# board.net
KiCad netlist of a schematic drawn in EAGLE
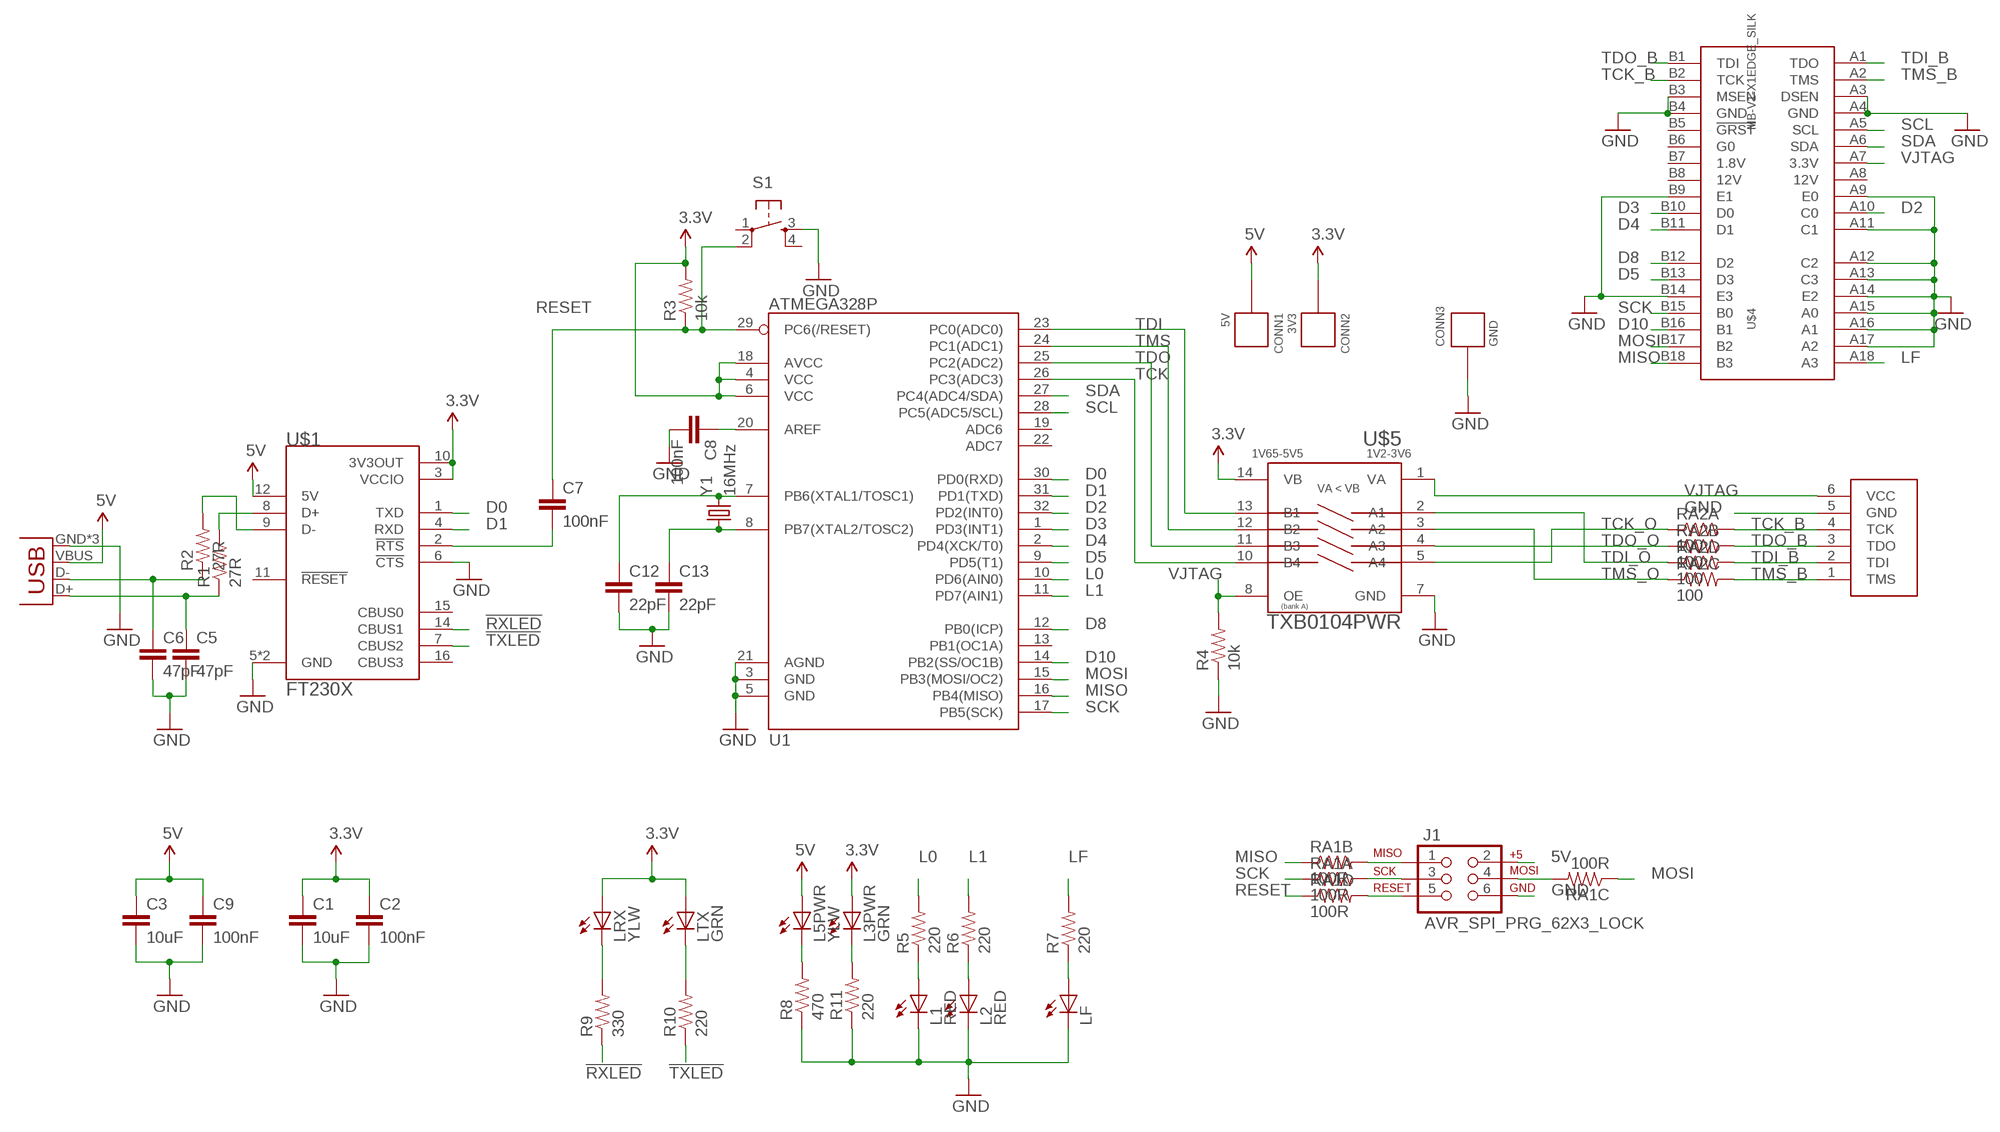
[diagram p0: schematic, sheet 1]

(export (version "E")
  (design (tool "Eeschema 10.0.6"))
  (components
    (comp (ref "C1")
      (value "10uF")
      (footprint "eagle-import:0805")
      (libsource (lib "eagle-import") (part "CAP0805"))
    )
    (comp (ref "C2")
      (value "100nF")
      (footprint "eagle-import:0402-CAP")
      (libsource (lib "eagle-import") (part "CAP0402-CAP"))
    )
    (comp (ref "C3")
      (value "10uF")
      (footprint "eagle-import:0805")
      (libsource (lib "eagle-import") (part "CAP0805"))
    )
    (comp (ref "C5")
      (value "47pF")
      (footprint "eagle-import:0402-CAP")
      (libsource (lib "eagle-import") (part "CAP0402-CAP"))
    )
    (comp (ref "C6")
      (value "47pF")
      (footprint "eagle-import:0402-CAP")
      (libsource (lib "eagle-import") (part "CAP0402-CAP"))
    )
    (comp (ref "C7")
      (value "100nF")
      (footprint "eagle-import:0402-CAP")
      (libsource (lib "eagle-import") (part "CAP0402-CAP"))
    )
    (comp (ref "C8")
      (value "100nF")
      (footprint "eagle-import:0402-CAP")
      (libsource (lib "eagle-import") (part "CAP0402-CAP"))
    )
    (comp (ref "C9")
      (value "100nF")
      (footprint "eagle-import:0402-CAP")
      (libsource (lib "eagle-import") (part "CAP0402-CAP"))
    )
    (comp (ref "C12")
      (value "22pF")
      (footprint "eagle-import:0402-CAP")
      (libsource (lib "eagle-import") (part "CAP0402-CAP"))
    )
    (comp (ref "C13")
      (value "22pF")
      (footprint "eagle-import:0402-CAP")
      (libsource (lib "eagle-import") (part "CAP0402-CAP"))
    )
    (comp (ref "CONN1")
      (value "5V")
      (footprint "eagle-import:HOLE_22AWG")
      (libsource (lib "eagle-import") (part "CONNECTOR22AWG"))
    )
    (comp (ref "CONN2")
      (value "3V3")
      (footprint "eagle-import:HOLE_22AWG")
      (libsource (lib "eagle-import") (part "CONNECTOR22AWG"))
    )
    (comp (ref "CONN3")
      (value "GND")
      (footprint "eagle-import:HOLE_22AWG")
      (libsource (lib "eagle-import") (part "CONNECTOR22AWG"))
    )
    (comp (ref "J1")
      (value "AVR_SPI_PRG_62X3_LOCK")
      (footprint "eagle-import:2X3_LOCK")
      (libsource (lib "eagle-import") (part "AVR_SPI_PRG_62X3_LOCK"))
    )
    (comp (ref "JP1")
      (value "USB-MICROB")
      (footprint "eagle-import:USB-MICROB")
      (libsource (lib "eagle-import") (part "USB-MICROB"))
    )
    (comp (ref "L1")
      (value "RED")
      (footprint "eagle-import:0603_LED")
      (libsource (lib "eagle-import") (part "LED0603"))
    )
    (comp (ref "L2")
      (value "RED")
      (footprint "eagle-import:0603_LED")
      (libsource (lib "eagle-import") (part "LED0603"))
    )
    (comp (ref "L3PWR")
      (value "GRN")
      (footprint "eagle-import:0603_LED")
      (libsource (lib "eagle-import") (part "LED0603"))
    )
    (comp (ref "L5PWR")
      (value "YLW")
      (footprint "eagle-import:0603_LED")
      (libsource (lib "eagle-import") (part "LED0603"))
    )
    (comp (ref "LF")
      (value "LED0603")
      (footprint "eagle-import:0603_LED")
      (libsource (lib "eagle-import") (part "LED0603"))
    )
    (comp (ref "LRX")
      (value "YLW")
      (footprint "eagle-import:0603_LED")
      (libsource (lib "eagle-import") (part "LED0603"))
    )
    (comp (ref "LTX")
      (value "GRN")
      (footprint "eagle-import:0603_LED")
      (libsource (lib "eagle-import") (part "LED0603"))
    )
    (comp (ref "R1")
      (value "27R")
      (footprint "eagle-import:0603-RES")
      (libsource (lib "eagle-import") (part "RESISTOR0603"))
    )
    (comp (ref "R2")
      (value "27R")
      (footprint "eagle-import:0603-RES")
      (libsource (lib "eagle-import") (part "RESISTOR0603"))
    )
    (comp (ref "R3")
      (value "10k")
      (footprint "eagle-import:0603-RES")
      (libsource (lib "eagle-import") (part "RESISTOR0603"))
    )
    (comp (ref "R4")
      (value "10k")
      (footprint "eagle-import:0603-RES")
      (libsource (lib "eagle-import") (part "RESISTOR0603"))
    )
    (comp (ref "R5")
      (value "220")
      (footprint "eagle-import:0603-RES")
      (libsource (lib "eagle-import") (part "RESISTOR0603"))
    )
    (comp (ref "R6")
      (value "220")
      (footprint "eagle-import:0603-RES")
      (libsource (lib "eagle-import") (part "RESISTOR0603"))
    )
    (comp (ref "R7")
      (value "220")
      (footprint "eagle-import:0603-RES")
      (libsource (lib "eagle-import") (part "RESISTOR0603"))
    )
    (comp (ref "R8")
      (value "470")
      (footprint "eagle-import:0603-RES")
      (libsource (lib "eagle-import") (part "RESISTOR0603"))
    )
    (comp (ref "R9")
      (value "330")
      (footprint "eagle-import:0603-RES")
      (libsource (lib "eagle-import") (part "RESISTOR0603"))
    )
    (comp (ref "R10")
      (value "220")
      (footprint "eagle-import:0603-RES")
      (libsource (lib "eagle-import") (part "RESISTOR0603"))
    )
    (comp (ref "R11")
      (value "220")
      (footprint "eagle-import:0603-RES")
      (libsource (lib "eagle-import") (part "RESISTOR0603"))
    )
    (comp (ref "RA1")
      (value "100R")
      (footprint "eagle-import:0603-ARV")
      (libsource (lib "eagle-import") (part "RESISTOR_ARRAY0603_X4"))
    )
    (comp (ref "RA2")
      (value "100")
      (footprint "eagle-import:0603-ARV")
      (libsource (lib "eagle-import") (part "RESISTOR_ARRAY0603_X4"))
    )
    (comp (ref "S1")
      (value "TAC_SWITCHPTH")
      (footprint "eagle-import:TACTILE-PTH")
      (libsource (lib "eagle-import") (part "TAC_SWITCHPTH"))
    )
    (comp (ref "U$1")
      (value "FT230X")
      (footprint "eagle-import:TSSOP16")
      (libsource (lib "eagle-import") (part "FT230X"))
    )
    (comp (ref "U$2")
      (value "JTAGDIGILENT")
      (footprint "eagle-import:1X06")
      (libsource (lib "eagle-import") (part "JTAGDIGILENT"))
    )
    (comp (ref "U$4")
      (value "MB-V1-X1EDGE_SILK")
      (footprint "eagle-import:MB-V1-X1-EDGE")
      (libsource (lib "eagle-import") (part "MB-V1-X1EDGE_SILK"))
    )
    (comp (ref "U$5")
      (value "TXB0104PWR")
      (footprint "eagle-import:TSSOP14")
      (libsource (lib "eagle-import") (part "TXB0104PWR"))
    )
    (comp (ref "U1")
      (value "ATMEGA328P")
      (footprint "eagle-import:TQFP32-08")
      (libsource (lib "eagle-import") (part "ATMEGA328_SMT"))
    )
    (comp (ref "Y1")
      (value "16MHz")
      (footprint "eagle-import:HC49US")
      (libsource (lib "eagle-import") (part "CRYSTALHC49US"))
    )
  )
  (nets
    (net (code "1") (name "/D0") (class "Default")
      (node (ref "U$1") (pin "1") (pinfunction "TXD_1") (pintype "bidirectional"))
      (node (ref "U1") (pin "30") (pinfunction "PD0(RXD)_30") (pintype "bidirectional"))
    )
    (net (code "2") (name "/D1") (class "Default")
      (node (ref "U$1") (pin "4") (pinfunction "RXD_4") (pintype "bidirectional"))
      (node (ref "U1") (pin "31") (pinfunction "PD1(TXD)_31") (pintype "bidirectional"))
    )
    (net (code "3") (name "/D2") (class "Default")
      (node (ref "U$4") (pin "A10") (pinfunction "C0_A10") (pintype "bidirectional"))
      (node (ref "U1") (pin "32") (pinfunction "PD2(INT0)_32") (pintype "bidirectional"))
    )
    (net (code "4") (name "/D3") (class "Default")
      (node (ref "U$4") (pin "B10") (pinfunction "D0_B10") (pintype "bidirectional"))
      (node (ref "U1") (pin "1") (pinfunction "PD3(INT1)_1") (pintype "bidirectional"))
    )
    (net (code "5") (name "/D4") (class "Default")
      (node (ref "U$4") (pin "B11") (pinfunction "D1_B11") (pintype "bidirectional"))
      (node (ref "U1") (pin "2") (pinfunction "PD4(XCK/T0)_2") (pintype "bidirectional"))
    )
    (net (code "6") (name "/D5") (class "Default")
      (node (ref "U$4") (pin "B13") (pinfunction "D3_B13") (pintype "bidirectional"))
      (node (ref "U1") (pin "9") (pinfunction "PD5(T1)_9") (pintype "bidirectional"))
    )
    (net (code "7") (name "/D8") (class "Default")
      (node (ref "U$4") (pin "B12") (pinfunction "D2_B12") (pintype "bidirectional"))
      (node (ref "U1") (pin "12") (pinfunction "PB0(ICP)_12") (pintype "bidirectional"))
    )
    (net (code "8") (name "/D10") (class "Default")
      (node (ref "U$4") (pin "B16") (pinfunction "B1_B16") (pintype "bidirectional"))
      (node (ref "U1") (pin "14") (pinfunction "PB2(SS/OC1B)_14") (pintype "bidirectional"))
    )
    (net (code "9") (name "/L0") (class "Default")
      (node (ref "R5") (pin "2") (pinfunction "2_2") (pintype "passive"))
      (node (ref "U1") (pin "10") (pinfunction "PD6(AIN0)_10") (pintype "bidirectional"))
    )
    (net (code "10") (name "/L1") (class "Default")
      (node (ref "R6") (pin "2") (pinfunction "2_2") (pintype "passive"))
      (node (ref "U1") (pin "11") (pinfunction "PD7(AIN1)_11") (pintype "bidirectional"))
    )
    (net (code "11") (name "/LF") (class "Default")
      (node (ref "R7") (pin "2") (pinfunction "2_2") (pintype "passive"))
      (node (ref "U$4") (pin "A18") (pinfunction "A3_A18") (pintype "bidirectional"))
    )
    (net (code "12") (name "/MISO") (class "Default")
      (node (ref "RA1") (pin "2") (pinfunction "1_2") (pintype "passive"))
      (node (ref "U$4") (pin "B18") (pinfunction "B3_B18") (pintype "bidirectional"))
      (node (ref "U1") (pin "16") (pinfunction "PB4(MISO)_16") (pintype "bidirectional"))
    )
    (net (code "13") (name "/MOSI") (class "Default")
      (node (ref "RA1") (pin "3") (pinfunction "1_3") (pintype "passive"))
      (node (ref "U$4") (pin "B17") (pinfunction "B2_B17") (pintype "bidirectional"))
      (node (ref "U1") (pin "15") (pinfunction "PB3(MOSI/OC2)_15") (pintype "bidirectional"))
    )
    (net (code "14") (name "/RESET") (class "Default")
      (node (ref "C7") (pin "1") (pinfunction "1_1") (pintype "passive"))
      (node (ref "R3") (pin "1") (pinfunction "1_1") (pintype "passive"))
      (node (ref "RA1") (pin "4") (pinfunction "1_4") (pintype "passive"))
      (node (ref "S1") (pin "2") (pinfunction "2_2") (pintype "passive"))
      (node (ref "U1") (pin "29") (pinfunction "PC6(/RESET)_29") (pintype "bidirectional"))
    )
    (net (code "15") (name "/SCK") (class "Default")
      (node (ref "RA1") (pin "1") (pinfunction "1_1") (pintype "passive"))
      (node (ref "U$4") (pin "B15") (pinfunction "B0_B15") (pintype "bidirectional"))
      (node (ref "U1") (pin "17") (pinfunction "PB5(SCK)_17") (pintype "bidirectional"))
    )
    (net (code "16") (name "/SCL") (class "Default")
      (node (ref "U$4") (pin "A5") (pinfunction "SCL_A5") (pintype "bidirectional"))
      (node (ref "U1") (pin "28") (pinfunction "PC5(ADC5/SCL)_28") (pintype "bidirectional"))
    )
    (net (code "17") (name "/SDA") (class "Default")
      (node (ref "U$4") (pin "A6") (pinfunction "SDA_A6") (pintype "bidirectional"))
      (node (ref "U1") (pin "27") (pinfunction "PC4(ADC4/SDA)_27") (pintype "bidirectional"))
    )
    (net (code "18") (name "/TCK") (class "Default")
      (node (ref "U$5") (pin "10") (pinfunction "B4_10") (pintype "bidirectional"))
      (node (ref "U1") (pin "26") (pinfunction "PC3(ADC3)_26") (pintype "bidirectional"))
    )
    (net (code "19") (name "/TCK_B") (class "Default")
      (node (ref "RA2") (pin "8") (pinfunction "2_8") (pintype "passive"))
      (node (ref "U$2") (pin "4") (pinfunction "TCK_4") (pintype "bidirectional"))
      (node (ref "U$4") (pin "B2") (pinfunction "TCK_B2") (pintype "bidirectional"))
    )
    (net (code "20") (name "/TCK_O") (class "Default")
      (node (ref "RA2") (pin "1") (pinfunction "1_1") (pintype "passive"))
      (node (ref "U$5") (pin "5") (pinfunction "A4_5") (pintype "bidirectional"))
    )
    (net (code "21") (name "/TDI") (class "Default")
      (node (ref "U$5") (pin "13") (pinfunction "B1_13") (pintype "bidirectional"))
      (node (ref "U1") (pin "23") (pinfunction "PC0(ADC0)_23") (pintype "bidirectional"))
    )
    (net (code "22") (name "/TDI_B") (class "Default")
      (node (ref "RA2") (pin "5") (pinfunction "2_5") (pintype "passive"))
      (node (ref "U$2") (pin "2") (pinfunction "TDI_2") (pintype "bidirectional"))
      (node (ref "U$4") (pin "A1") (pinfunction "TDO_A1") (pintype "bidirectional"))
    )
    (net (code "23") (name "/TDI_O") (class "Default")
      (node (ref "RA2") (pin "4") (pinfunction "1_4") (pintype "passive"))
      (node (ref "U$5") (pin "2") (pinfunction "A1_2") (pintype "bidirectional"))
    )
    (net (code "24") (name "/TDO") (class "Default")
      (node (ref "U$5") (pin "11") (pinfunction "B3_11") (pintype "bidirectional"))
      (node (ref "U1") (pin "25") (pinfunction "PC2(ADC2)_25") (pintype "bidirectional"))
    )
    (net (code "25") (name "/TDO_B") (class "Default")
      (node (ref "RA2") (pin "7") (pinfunction "2_7") (pintype "passive"))
      (node (ref "U$2") (pin "3") (pinfunction "TDO_3") (pintype "bidirectional"))
      (node (ref "U$4") (pin "B1") (pinfunction "TDI_B1") (pintype "bidirectional"))
    )
    (net (code "26") (name "/TDO_O") (class "Default")
      (node (ref "RA2") (pin "2") (pinfunction "1_2") (pintype "passive"))
      (node (ref "U$5") (pin "4") (pinfunction "A3_4") (pintype "bidirectional"))
    )
    (net (code "27") (name "/TMS") (class "Default")
      (node (ref "U$5") (pin "12") (pinfunction "B2_12") (pintype "bidirectional"))
      (node (ref "U1") (pin "24") (pinfunction "PC1(ADC1)_24") (pintype "bidirectional"))
    )
    (net (code "28") (name "/TMS_B") (class "Default")
      (node (ref "RA2") (pin "6") (pinfunction "2_6") (pintype "passive"))
      (node (ref "U$2") (pin "1") (pinfunction "TMS_1") (pintype "bidirectional"))
      (node (ref "U$4") (pin "A2") (pinfunction "TMS_A2") (pintype "bidirectional"))
    )
    (net (code "29") (name "/TMS_O") (class "Default")
      (node (ref "RA2") (pin "3") (pinfunction "1_3") (pintype "passive"))
      (node (ref "U$5") (pin "3") (pinfunction "A2_3") (pintype "bidirectional"))
    )
    (net (code "30") (name "/VJTAG") (class "Default")
      (node (ref "R4") (pin "2") (pinfunction "2_2") (pintype "passive"))
      (node (ref "U$2") (pin "6") (pinfunction "VCC_6") (pintype "bidirectional"))
      (node (ref "U$4") (pin "A7") (pinfunction "3.3V_A7") (pintype "bidirectional"))
      (node (ref "U$5") (pin "1") (pinfunction "VA_1") (pintype "bidirectional"))
      (node (ref "U$5") (pin "8") (pinfunction "OE_8") (pintype "bidirectional"))
    )
    (net (code "31") (name "/~{RXLED}") (class "Default")
      (node (ref "R9") (pin "1") (pinfunction "1_1") (pintype "passive"))
      (node (ref "U$1") (pin "14") (pinfunction "CBUS1_14") (pintype "bidirectional"))
    )
    (net (code "32") (name "/~{TXLED}") (class "Default")
      (node (ref "R10") (pin "1") (pinfunction "1_1") (pintype "passive"))
      (node (ref "U$1") (pin "7") (pinfunction "CBUS2_7") (pintype "bidirectional"))
    )
    (net (code "33") (name "3.3V") (class "Default")
      (node (ref "C1") (pin "1") (pinfunction "1_1") (pintype "passive"))
      (node (ref "C2") (pin "1") (pinfunction "1_1") (pintype "passive"))
      (node (ref "CONN2") (pin "P") (pinfunction "P_P") (pintype "bidirectional"))
      (node (ref "L3PWR") (pin "A") (pinfunction "A_A") (pintype "passive"))
      (node (ref "LRX") (pin "A") (pinfunction "A_A") (pintype "passive"))
      (node (ref "LTX") (pin "A") (pinfunction "A_A") (pintype "passive"))
      (node (ref "R3") (pin "2") (pinfunction "2_2") (pintype "passive"))
      (node (ref "U$1") (pin "10") (pinfunction "3V3OUT_10") (pintype "bidirectional"))
      (node (ref "U$1") (pin "3") (pinfunction "VCCIO_3") (pintype "bidirectional"))
      (node (ref "U$5") (pin "14") (pinfunction "VB_14") (pintype "bidirectional"))
      (node (ref "U1") (pin "18") (pinfunction "AVCC_18") (pintype "bidirectional"))
      (node (ref "U1") (pin "4") (pinfunction "VCC_4") (pintype "bidirectional"))
      (node (ref "U1") (pin "6") (pinfunction "VCC_6") (pintype "bidirectional"))
    )
    (net (code "34") (name "5V") (class "Default")
      (node (ref "C3") (pin "1") (pinfunction "1_1") (pintype "passive"))
      (node (ref "C9") (pin "1") (pinfunction "1_1") (pintype "passive"))
      (node (ref "CONN1") (pin "P") (pinfunction "P_P") (pintype "bidirectional"))
      (node (ref "J1") (pin "2") (pinfunction "2_2") (pintype "passive"))
      (node (ref "JP1") (pin "VBUS") (pinfunction "VBUS_VBUS") (pintype "bidirectional"))
      (node (ref "L5PWR") (pin "A") (pinfunction "A_A") (pintype "passive"))
      (node (ref "U$1") (pin "12") (pinfunction "5V_12") (pintype "bidirectional"))
    )
    (net (code "35") (name "GND") (class "Default")
      (node (ref "C1") (pin "2") (pinfunction "2_2") (pintype "passive"))
      (node (ref "C12") (pin "2") (pinfunction "2_2") (pintype "passive"))
      (node (ref "C13") (pin "2") (pinfunction "2_2") (pintype "passive"))
      (node (ref "C2") (pin "2") (pinfunction "2_2") (pintype "passive"))
      (node (ref "C3") (pin "2") (pinfunction "2_2") (pintype "passive"))
      (node (ref "C5") (pin "2") (pinfunction "2_2") (pintype "passive"))
      (node (ref "C6") (pin "2") (pinfunction "2_2") (pintype "passive"))
      (node (ref "C8") (pin "2") (pinfunction "2_2") (pintype "passive"))
      (node (ref "C9") (pin "2") (pinfunction "2_2") (pintype "passive"))
      (node (ref "CONN3") (pin "P") (pinfunction "P_P") (pintype "bidirectional"))
      (node (ref "J1") (pin "6") (pinfunction "6_6") (pintype "passive"))
      (node (ref "JP1") (pin "GND") (pinfunction "GND_GND") (pintype "bidirectional"))
      (node (ref "JP1") (pin "MT1") (pinfunction "GND_MT1") (pintype "bidirectional"))
      (node (ref "JP1") (pin "MT2") (pinfunction "GND_MT2") (pintype "bidirectional"))
      (node (ref "L1") (pin "C") (pinfunction "C_C") (pintype "passive"))
      (node (ref "L2") (pin "C") (pinfunction "C_C") (pintype "passive"))
      (node (ref "LF") (pin "C") (pinfunction "C_C") (pintype "passive"))
      (node (ref "R11") (pin "1") (pinfunction "1_1") (pintype "passive"))
      (node (ref "R4") (pin "1") (pinfunction "1_1") (pintype "passive"))
      (node (ref "R8") (pin "1") (pinfunction "1_1") (pintype "passive"))
      (node (ref "S1") (pin "3") (pinfunction "3_3") (pintype "passive"))
      (node (ref "U$1") (pin "13") (pinfunction "GND_13") (pintype "bidirectional"))
      (node (ref "U$1") (pin "5") (pinfunction "GND_5") (pintype "bidirectional"))
      (node (ref "U$1") (pin "6") (pinfunction "~{CTS}_6") (pintype "bidirectional"))
      (node (ref "U$2") (pin "5") (pinfunction "GND_5") (pintype "bidirectional"))
      (node (ref "U$4") (pin "A11") (pinfunction "C1_A11") (pintype "bidirectional"))
      (node (ref "U$4") (pin "A12") (pinfunction "C2_A12") (pintype "bidirectional"))
      (node (ref "U$4") (pin "A13") (pinfunction "C3_A13") (pintype "bidirectional"))
      (node (ref "U$4") (pin "A14") (pinfunction "E2_A14") (pintype "bidirectional"))
      (node (ref "U$4") (pin "A15") (pinfunction "A0_A15") (pintype "bidirectional"))
      (node (ref "U$4") (pin "A16") (pinfunction "A1_A16") (pintype "bidirectional"))
      (node (ref "U$4") (pin "A17") (pinfunction "A2_A17") (pintype "bidirectional"))
      (node (ref "U$4") (pin "A3") (pinfunction "DSEN_A3") (pintype "bidirectional"))
      (node (ref "U$4") (pin "A4") (pinfunction "GND_A4") (pintype "bidirectional"))
      (node (ref "U$4") (pin "A9") (pinfunction "E0_A9") (pintype "bidirectional"))
      (node (ref "U$4") (pin "B14") (pinfunction "E3_B14") (pintype "bidirectional"))
      (node (ref "U$4") (pin "B3") (pinfunction "MSEN_B3") (pintype "bidirectional"))
      (node (ref "U$4") (pin "B4") (pinfunction "GND_B4") (pintype "bidirectional"))
      (node (ref "U$4") (pin "B9") (pinfunction "E1_B9") (pintype "bidirectional"))
      (node (ref "U$5") (pin "7") (pinfunction "GND_7") (pintype "bidirectional"))
      (node (ref "U1") (pin "21") (pinfunction "AGND_21") (pintype "bidirectional"))
      (node (ref "U1") (pin "3") (pinfunction "GND_3") (pintype "bidirectional"))
      (node (ref "U1") (pin "5") (pinfunction "GND_5") (pintype "bidirectional"))
    )
    (net (code "36") (name "Net-(C5-Pad1)") (class "Default")
      (node (ref "C5") (pin "1") (pinfunction "1_1") (pintype "passive"))
      (node (ref "JP1") (pin "D+") (pinfunction "D+_D+") (pintype "bidirectional"))
      (node (ref "R1") (pin "1") (pinfunction "1_1") (pintype "passive"))
    )
    (net (code "37") (name "Net-(C6-Pad1)") (class "Default")
      (node (ref "C6") (pin "1") (pinfunction "1_1") (pintype "passive"))
      (node (ref "JP1") (pin "D-") (pinfunction "D-_D-") (pintype "bidirectional"))
      (node (ref "R2") (pin "1") (pinfunction "1_1") (pintype "passive"))
    )
    (net (code "38") (name "Net-(L1-PadA)") (class "Default")
      (node (ref "L1") (pin "A") (pinfunction "A_A") (pintype "passive"))
      (node (ref "R5") (pin "1") (pinfunction "1_1") (pintype "passive"))
    )
    (net (code "39") (name "Net-(L2-PadA)") (class "Default")
      (node (ref "L2") (pin "A") (pinfunction "A_A") (pintype "passive"))
      (node (ref "R6") (pin "1") (pinfunction "1_1") (pintype "passive"))
    )
    (net (code "40") (name "Net-(L3PWR-PadC)") (class "Default")
      (node (ref "L3PWR") (pin "C") (pinfunction "C_C") (pintype "passive"))
      (node (ref "R11") (pin "2") (pinfunction "2_2") (pintype "passive"))
    )
    (net (code "41") (name "Net-(L5PWR-PadC)") (class "Default")
      (node (ref "L5PWR") (pin "C") (pinfunction "C_C") (pintype "passive"))
      (node (ref "R8") (pin "2") (pinfunction "2_2") (pintype "passive"))
    )
    (net (code "42") (name "Net-(LF-PadA)") (class "Default")
      (node (ref "LF") (pin "A") (pinfunction "A_A") (pintype "passive"))
      (node (ref "R7") (pin "1") (pinfunction "1_1") (pintype "passive"))
    )
    (net (code "43") (name "Net-(LRX-PadC)") (class "Default")
      (node (ref "LRX") (pin "C") (pinfunction "C_C") (pintype "passive"))
      (node (ref "R9") (pin "2") (pinfunction "2_2") (pintype "passive"))
    )
    (net (code "44") (name "Net-(LTX-PadC)") (class "Default")
      (node (ref "LTX") (pin "C") (pinfunction "C_C") (pintype "passive"))
      (node (ref "R10") (pin "2") (pinfunction "2_2") (pintype "passive"))
    )
    (net (code "45") (name "Net-(RA1A-2)") (class "Default")
      (node (ref "J1") (pin "3") (pinfunction "3_3") (pintype "passive"))
      (node (ref "RA1") (pin "8") (pinfunction "2_8") (pintype "passive"))
    )
    (net (code "46") (name "Net-(RA1B-2)") (class "Default")
      (node (ref "J1") (pin "1") (pinfunction "1_1") (pintype "passive"))
      (node (ref "RA1") (pin "7") (pinfunction "2_7") (pintype "passive"))
    )
    (net (code "47") (name "Net-(RA1C-2)") (class "Default")
      (node (ref "J1") (pin "4") (pinfunction "4_4") (pintype "passive"))
      (node (ref "RA1") (pin "6") (pinfunction "2_6") (pintype "passive"))
    )
    (net (code "48") (name "Net-(RA1D-2)") (class "Default")
      (node (ref "J1") (pin "5") (pinfunction "5_5") (pintype "passive"))
      (node (ref "RA1") (pin "5") (pinfunction "2_5") (pintype "passive"))
    )
    (net (code "49") (name "Net-(U$1-D+)") (class "Default")
      (node (ref "R1") (pin "2") (pinfunction "2_2") (pintype "passive"))
      (node (ref "U$1") (pin "8") (pinfunction "D+_8") (pintype "bidirectional"))
    )
    (net (code "50") (name "Net-(U$1-D-)") (class "Default")
      (node (ref "R2") (pin "2") (pinfunction "2_2") (pintype "passive"))
      (node (ref "U$1") (pin "9") (pinfunction "D-_9") (pintype "bidirectional"))
    )
    (net (code "51") (name "Net-(U$1-~{RTS})") (class "Default")
      (node (ref "C7") (pin "2") (pinfunction "2_2") (pintype "passive"))
      (node (ref "U$1") (pin "2") (pinfunction "~{RTS}_2") (pintype "bidirectional"))
    )
    (net (code "52") (name "Net-(U1-AREF)") (class "Default")
      (node (ref "C8") (pin "1") (pinfunction "1_1") (pintype "passive"))
      (node (ref "U1") (pin "20") (pinfunction "AREF_20") (pintype "bidirectional"))
    )
    (net (code "53") (name "Net-(U1-PB6(XTAL1{slash}TOSC1))") (class "Default")
      (node (ref "C12") (pin "1") (pinfunction "1_1") (pintype "passive"))
      (node (ref "U1") (pin "7") (pinfunction "PB6(XTAL1/TOSC1)_7") (pintype "bidirectional"))
      (node (ref "Y1") (pin "2") (pinfunction "2_2") (pintype "passive"))
    )
    (net (code "54") (name "Net-(U1-PB7(XTAL2{slash}TOSC2))") (class "Default")
      (node (ref "C13") (pin "1") (pinfunction "1_1") (pintype "passive"))
      (node (ref "U1") (pin "8") (pinfunction "PB7(XTAL2/TOSC2)_8") (pintype "bidirectional"))
      (node (ref "Y1") (pin "1") (pinfunction "1_1") (pintype "passive"))
    )
    (net (code "55") (name "unconnected-(S1-Pad1)") (class "Default")
      (node (ref "S1") (pin "1") (pinfunction "1_1") (pintype "passive"))
    )
    (net (code "56") (name "unconnected-(S1-Pad4)") (class "Default")
      (node (ref "S1") (pin "4") (pinfunction "4_4") (pintype "passive"))
    )
    (net (code "57") (name "unconnected-(U$1-CBUS0-Pad15)") (class "Default")
      (node (ref "U$1") (pin "15") (pinfunction "CBUS0_15") (pintype "bidirectional"))
    )
    (net (code "58") (name "unconnected-(U$1-CBUS3-Pad16)") (class "Default")
      (node (ref "U$1") (pin "16") (pinfunction "CBUS3_16") (pintype "bidirectional"))
    )
    (net (code "59") (name "unconnected-(U$1-~{RESET}-Pad11)") (class "Default")
      (node (ref "U$1") (pin "11") (pinfunction "~{RESET}_11") (pintype "bidirectional"))
    )
    (net (code "60") (name "unconnected-(U$4-1.8V-PadB7)") (class "Default")
      (node (ref "U$4") (pin "B7") (pinfunction "1.8V_B7") (pintype "bidirectional"))
    )
    (net (code "61") (name "unconnected-(U$4-12V-PadA8)") (class "Default")
      (node (ref "U$4") (pin "A8") (pinfunction "12V_A8") (pintype "bidirectional"))
    )
    (net (code "62") (name "unconnected-(U$4-12V-PadB8)") (class "Default")
      (node (ref "U$4") (pin "B8") (pinfunction "12V_B8") (pintype "bidirectional"))
    )
    (net (code "63") (name "unconnected-(U$4-G0-PadB6)") (class "Default")
      (node (ref "U$4") (pin "B6") (pinfunction "G0_B6") (pintype "bidirectional"))
    )
    (net (code "64") (name "unconnected-(U$4-~{GRST}-PadB5)") (class "Default")
      (node (ref "U$4") (pin "B5") (pinfunction "~{GRST}_B5") (pintype "bidirectional"))
    )
    (net (code "65") (name "unconnected-(U1-ADC6-Pad19)") (class "Default")
      (node (ref "U1") (pin "19") (pinfunction "ADC6_19") (pintype "bidirectional"))
    )
    (net (code "66") (name "unconnected-(U1-ADC7-Pad22)") (class "Default")
      (node (ref "U1") (pin "22") (pinfunction "ADC7_22") (pintype "bidirectional"))
    )
    (net (code "67") (name "unconnected-(U1-PB1(OC1A)-Pad13)") (class "Default")
      (node (ref "U1") (pin "13") (pinfunction "PB1(OC1A)_13") (pintype "bidirectional"))
    )
  )
)
